# SPPM.net
KiCad netlist of a schematic drawn in EAGLE
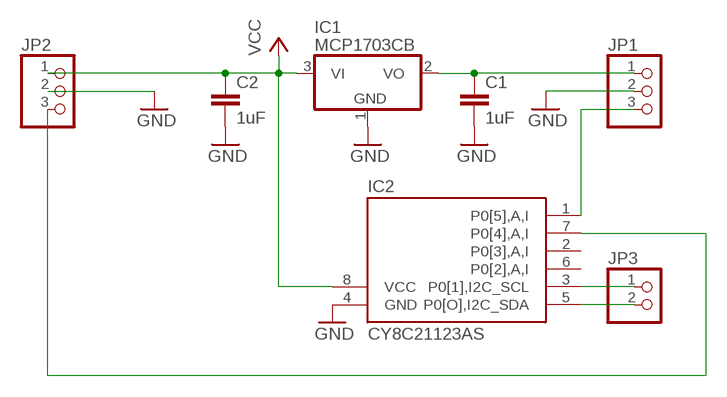
[diagram p0: schematic, sheet 1]

(export (version "E")
  (design (tool "Eeschema 10.0.6"))
  (components
    (comp (ref "C1")
      (value "1uF")
      (footprint "eagle-import:C0805")
      (libsource (lib "eagle-import") (part "C-EUC0805"))
    )
    (comp (ref "C2")
      (value "1uF")
      (footprint "eagle-import:C0805")
      (libsource (lib "eagle-import") (part "C-EUC0805"))
    )
    (comp (ref "IC1")
      (value "MCP1703CB")
      (footprint "eagle-import:SOT23")
      (libsource (lib "eagle-import") (part "MCP1703CB"))
    )
    (comp (ref "IC2")
      (value "CY8C21123AS")
      (footprint "eagle-import:SOIC8")
      (libsource (lib "eagle-import") (part "CY8C21123AS"))
    )
    (comp (ref "JP1")
      (value "PINHD-1X3")
      (footprint "eagle-import:1X03")
      (libsource (lib "eagle-import") (part "PINHD-1X3"))
    )
    (comp (ref "JP2")
      (value "PINHD-1X3")
      (footprint "eagle-import:1X03")
      (libsource (lib "eagle-import") (part "PINHD-1X3"))
    )
    (comp (ref "JP3")
      (value "PINHD-1X2")
      (footprint "eagle-import:1X02")
      (libsource (lib "eagle-import") (part "PINHD-1X2"))
    )
  )
  (nets
    (net (code "1") (name "GND") (class "Default")
      (node (ref "C1") (pin "2") (pinfunction "2_2") (pintype "passive"))
      (node (ref "C2") (pin "2") (pinfunction "2_2") (pintype "passive"))
      (node (ref "IC1") (pin "1") (pinfunction "GND_1") (pintype "passive"))
      (node (ref "IC2") (pin "4") (pinfunction "GND_4") (pintype "power_in"))
      (node (ref "JP1") (pin "2") (pinfunction "2_2") (pintype "passive"))
      (node (ref "JP2") (pin "2") (pinfunction "2_2") (pintype "passive"))
    )
    (net (code "2") (name "Net-(IC1-VO)") (class "Default")
      (node (ref "C1") (pin "1") (pinfunction "1_1") (pintype "passive"))
      (node (ref "IC1") (pin "2") (pinfunction "VO_2") (pintype "passive"))
      (node (ref "JP1") (pin "1") (pinfunction "1_1") (pintype "passive"))
    )
    (net (code "3") (name "Net-(IC2-P0[1],I2C_SCL)") (class "Default")
      (node (ref "IC2") (pin "3") (pinfunction "P0[1],I2C_SCL_3") (pintype "bidirectional"))
      (node (ref "JP3") (pin "1") (pinfunction "1_1") (pintype "passive"))
    )
    (net (code "4") (name "Net-(IC2-P0[4],A,I)") (class "Default")
      (node (ref "IC2") (pin "7") (pinfunction "P0[4],A,I_7") (pintype "bidirectional"))
      (node (ref "JP2") (pin "3") (pinfunction "3_3") (pintype "passive"))
    )
    (net (code "5") (name "Net-(IC2-P0[5],A,I)") (class "Default")
      (node (ref "IC2") (pin "1") (pinfunction "P0[5],A,I_1") (pintype "bidirectional"))
      (node (ref "JP1") (pin "3") (pinfunction "3_3") (pintype "passive"))
    )
    (net (code "6") (name "Net-(IC2-P0[O],I2C_SDA)") (class "Default")
      (node (ref "IC2") (pin "5") (pinfunction "P0[O],I2C_SDA_5") (pintype "bidirectional"))
      (node (ref "JP3") (pin "2") (pinfunction "2_2") (pintype "passive"))
    )
    (net (code "7") (name "VCC") (class "Default")
      (node (ref "C2") (pin "1") (pinfunction "1_1") (pintype "passive"))
      (node (ref "IC1") (pin "3") (pinfunction "VI_3") (pintype "input"))
      (node (ref "IC2") (pin "8") (pinfunction "VCC_8") (pintype "power_in"))
      (node (ref "JP2") (pin "1") (pinfunction "1_1") (pintype "passive"))
    )
    (net (code "8") (name "unconnected-(IC2-P0[2],A,I-Pad6)") (class "Default")
      (node (ref "IC2") (pin "6") (pinfunction "P0[2],A,I_6") (pintype "bidirectional"))
    )
    (net (code "9") (name "unconnected-(IC2-P0[3],A,I-Pad2)") (class "Default")
      (node (ref "IC2") (pin "2") (pinfunction "P0[3],A,I_2") (pintype "bidirectional"))
    )
  )
)
